# untitled.net
KiCad netlist of a schematic drawn in EAGLE
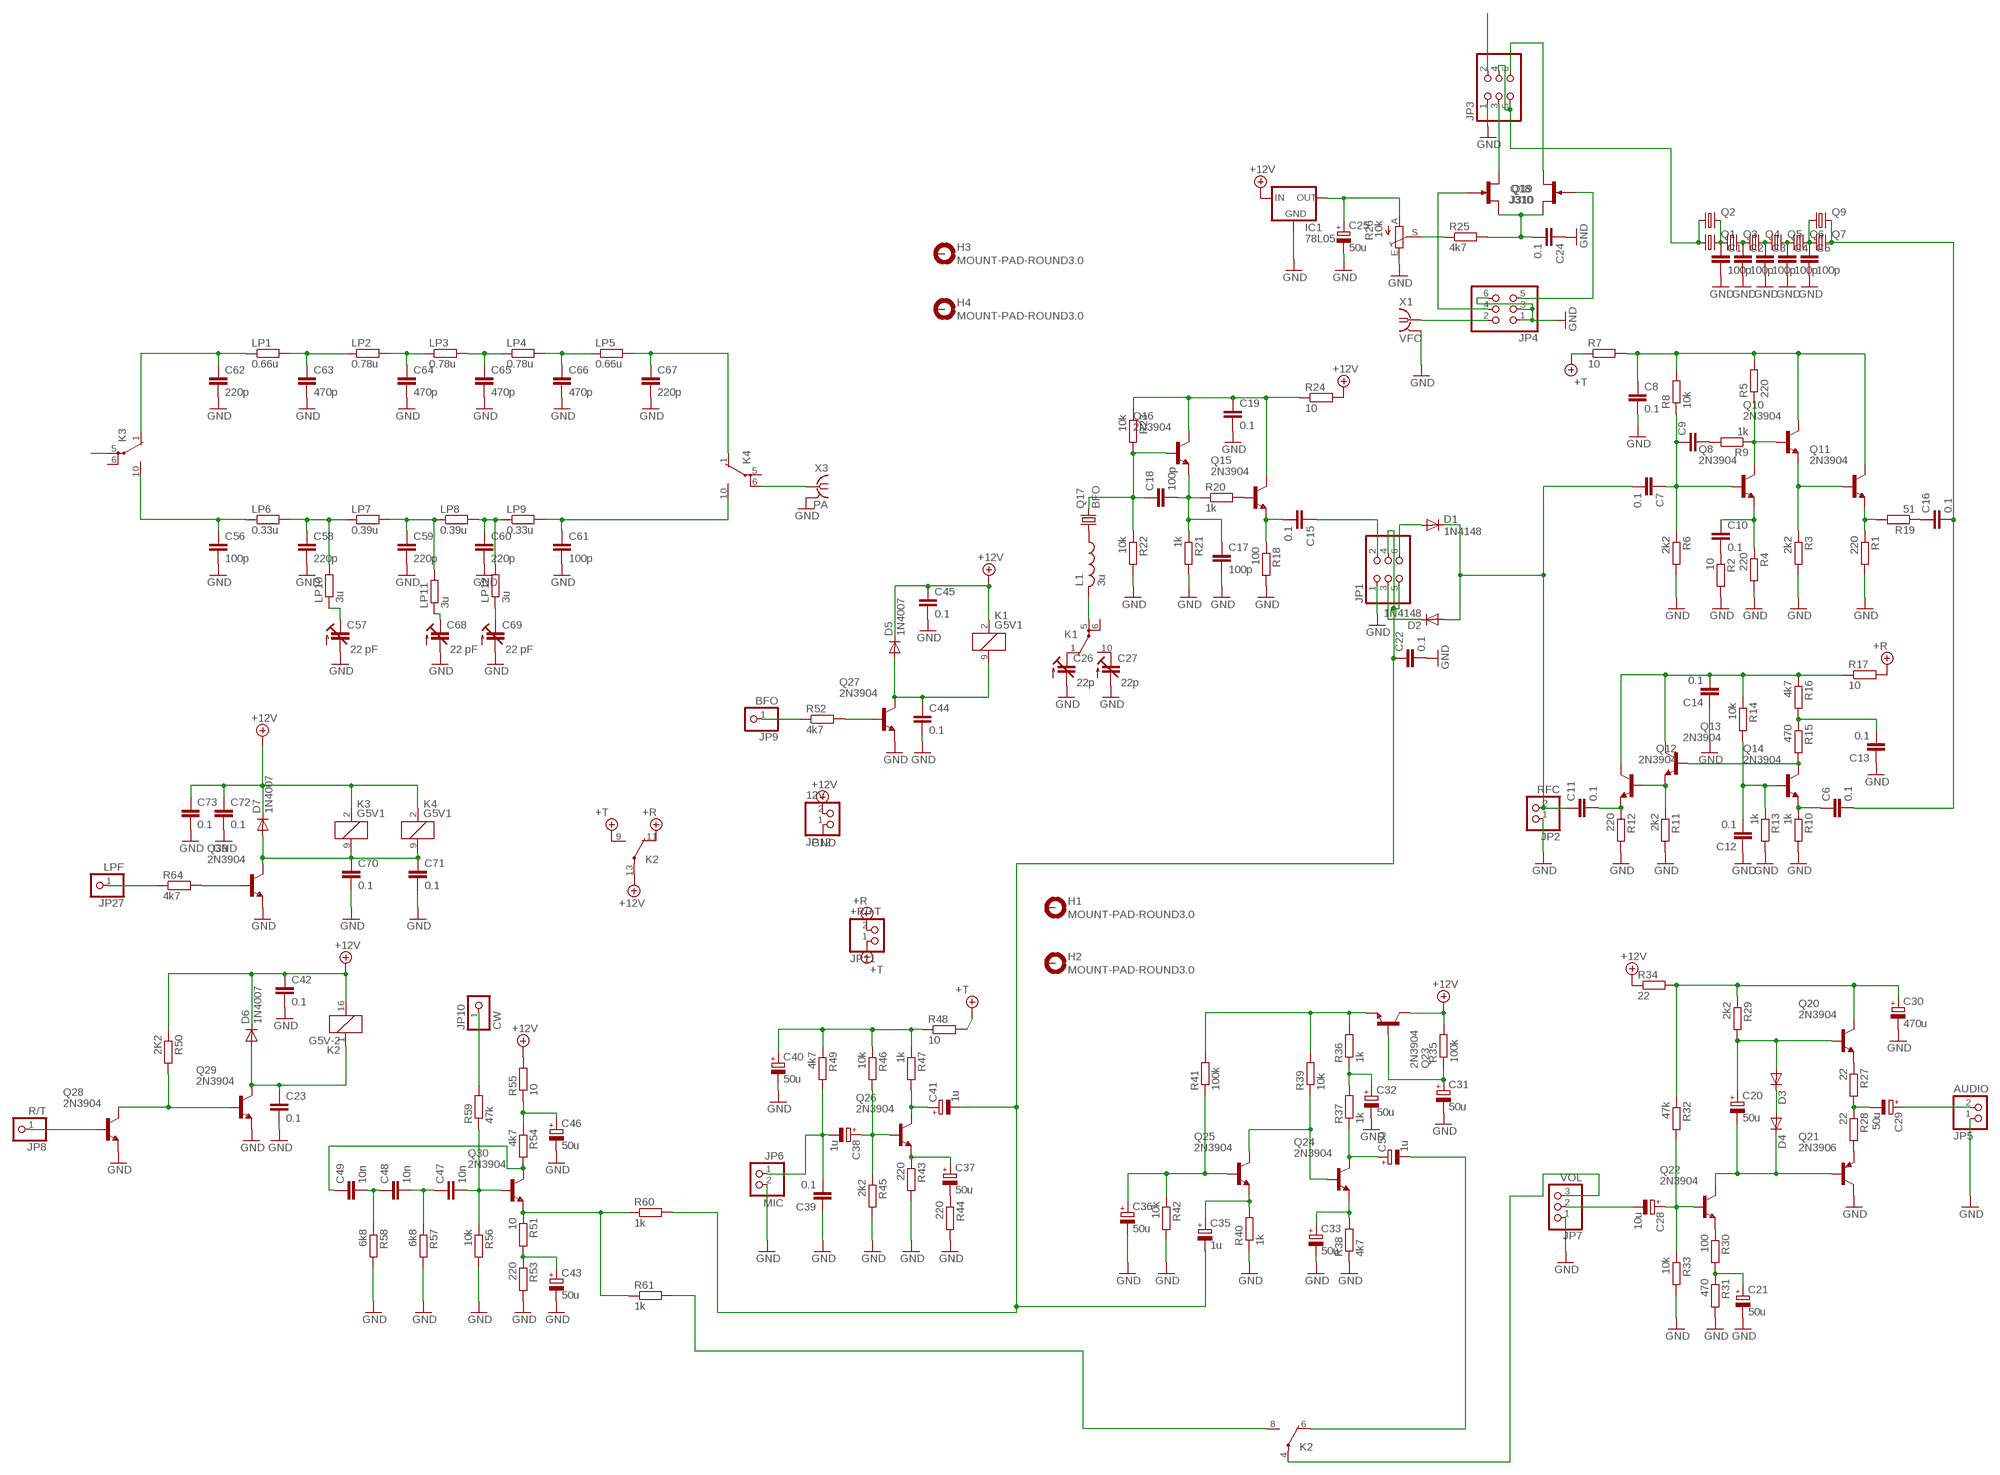
[diagram p0: schematic, sheet 1]

(export (version "E")
  (design (tool "Eeschema 10.0.6"))
  (components
    (comp (ref "C1")
      (value "100p")
      (footprint "eagle-import:C1206")
      (libsource (lib "eagle-import") (part "C-EUC1206"))
    )
    (comp (ref "C2")
      (value "100p")
      (footprint "eagle-import:C1206")
      (libsource (lib "eagle-import") (part "C-EUC1206"))
    )
    (comp (ref "C3")
      (value "100p")
      (footprint "eagle-import:C1206")
      (libsource (lib "eagle-import") (part "C-EUC1206"))
    )
    (comp (ref "C4")
      (value "100p")
      (footprint "eagle-import:C1206")
      (libsource (lib "eagle-import") (part "C-EUC1206"))
    )
    (comp (ref "C5")
      (value "100p")
      (footprint "eagle-import:C1206")
      (libsource (lib "eagle-import") (part "C-EUC1206"))
    )
    (comp (ref "C6")
      (value "0.1")
      (footprint "eagle-import:C050-024X044")
      (libsource (lib "eagle-import") (part "C-EU050-024X044"))
    )
    (comp (ref "C7")
      (value "0.1")
      (footprint "eagle-import:C050-024X044")
      (libsource (lib "eagle-import") (part "C-EU050-024X044"))
    )
    (comp (ref "C8")
      (value "0.1")
      (footprint "eagle-import:C050-024X044")
      (libsource (lib "eagle-import") (part "C-EU050-024X044"))
    )
    (comp (ref "C9")
      (value "C-EU050-024X044")
      (footprint "eagle-import:C050-024X044")
      (libsource (lib "eagle-import") (part "C-EU050-024X044"))
    )
    (comp (ref "C10")
      (value "0.1")
      (footprint "eagle-import:C050-024X044")
      (libsource (lib "eagle-import") (part "C-EU050-024X044"))
    )
    (comp (ref "C11")
      (value "0.1")
      (footprint "eagle-import:C050-024X044")
      (libsource (lib "eagle-import") (part "C-EU050-024X044"))
    )
    (comp (ref "C12")
      (value "0.1")
      (footprint "eagle-import:C050-024X044")
      (libsource (lib "eagle-import") (part "C-EU050-024X044"))
    )
    (comp (ref "C13")
      (value "0.1")
      (footprint "eagle-import:C050-024X044")
      (libsource (lib "eagle-import") (part "C-EU050-024X044"))
    )
    (comp (ref "C14")
      (value "0.1")
      (footprint "eagle-import:C050-024X044")
      (libsource (lib "eagle-import") (part "C-EU050-024X044"))
    )
    (comp (ref "C15")
      (value "0.1")
      (footprint "eagle-import:C050-024X044")
      (libsource (lib "eagle-import") (part "C-EU050-024X044"))
    )
    (comp (ref "C16")
      (value "0.1")
      (footprint "eagle-import:C050-024X044")
      (libsource (lib "eagle-import") (part "C-EU050-024X044"))
    )
    (comp (ref "C17")
      (value "100p")
      (footprint "eagle-import:C050-024X044")
      (libsource (lib "eagle-import") (part "C-EU050-024X044"))
    )
    (comp (ref "C18")
      (value "100p")
      (footprint "eagle-import:C050-024X044")
      (libsource (lib "eagle-import") (part "C-EU050-024X044"))
    )
    (comp (ref "C19")
      (value "0.1")
      (footprint "eagle-import:C050-024X044")
      (libsource (lib "eagle-import") (part "C-EU050-024X044"))
    )
    (comp (ref "C20")
      (value "50u")
      (footprint "eagle-import:E2,5-5")
      (libsource (lib "eagle-import") (part "CPOL-EUE2.5-5"))
    )
    (comp (ref "C21")
      (value "50u")
      (footprint "eagle-import:E2,5-5")
      (libsource (lib "eagle-import") (part "CPOL-EUE2.5-5"))
    )
    (comp (ref "C22")
      (value "0.1")
      (footprint "eagle-import:C050-024X044")
      (libsource (lib "eagle-import") (part "C-EU050-024X044"))
    )
    (comp (ref "C23")
      (value "0.1")
      (footprint "eagle-import:C050-024X044")
      (libsource (lib "eagle-import") (part "C-EU050-024X044"))
    )
    (comp (ref "C24")
      (value "0.1")
      (footprint "eagle-import:C050-024X044")
      (libsource (lib "eagle-import") (part "C-EU050-024X044"))
    )
    (comp (ref "C25")
      (value "50u")
      (footprint "eagle-import:E2,5-5")
      (libsource (lib "eagle-import") (part "CPOL-EUE2.5-5"))
    )
    (comp (ref "C26")
      (value "22p")
      (footprint "eagle-import:CTRIMTZ03")
      (libsource (lib "eagle-import") (part "C-TRIMMTZ03"))
    )
    (comp (ref "C27")
      (value "22p")
      (footprint "eagle-import:CTRIMTZ03")
      (libsource (lib "eagle-import") (part "C-TRIMMTZ03"))
    )
    (comp (ref "C28")
      (value "10u")
      (footprint "eagle-import:E2,5-5")
      (libsource (lib "eagle-import") (part "CPOL-EUE2.5-5"))
    )
    (comp (ref "C29")
      (value "50u")
      (footprint "eagle-import:E2,5-5")
      (libsource (lib "eagle-import") (part "CPOL-EUE2.5-5"))
    )
    (comp (ref "C30")
      (value "470u")
      (footprint "eagle-import:E2,5-5")
      (libsource (lib "eagle-import") (part "CPOL-EUE2.5-5"))
    )
    (comp (ref "C31")
      (value "50u")
      (footprint "eagle-import:E2,5-5")
      (libsource (lib "eagle-import") (part "CPOL-EUE2.5-5"))
    )
    (comp (ref "C32")
      (value "50u")
      (footprint "eagle-import:E2,5-5")
      (libsource (lib "eagle-import") (part "CPOL-EUE2.5-5"))
    )
    (comp (ref "C33")
      (value "50u")
      (footprint "eagle-import:E2,5-5")
      (libsource (lib "eagle-import") (part "CPOL-EUE2.5-5"))
    )
    (comp (ref "C35")
      (value "1u")
      (footprint "eagle-import:E2,5-5")
      (libsource (lib "eagle-import") (part "CPOL-EUE2.5-5"))
    )
    (comp (ref "C36")
      (value "50u")
      (footprint "eagle-import:E2,5-5")
      (libsource (lib "eagle-import") (part "CPOL-EUE2.5-5"))
    )
    (comp (ref "C37")
      (value "50u")
      (footprint "eagle-import:E2,5-5")
      (libsource (lib "eagle-import") (part "CPOL-EUE2.5-5"))
    )
    (comp (ref "C38")
      (value "1u")
      (footprint "eagle-import:E2,5-5")
      (libsource (lib "eagle-import") (part "CPOL-EUE2.5-5"))
    )
    (comp (ref "C39")
      (value "0.1")
      (footprint "eagle-import:C050-024X044")
      (libsource (lib "eagle-import") (part "C-EU050-024X044"))
    )
    (comp (ref "C40")
      (value "50u")
      (footprint "eagle-import:E2,5-5")
      (libsource (lib "eagle-import") (part "CPOL-EUE2.5-5"))
    )
    (comp (ref "C41")
      (value "1u")
      (footprint "eagle-import:E2,5-5")
      (libsource (lib "eagle-import") (part "CPOL-EUE2.5-5"))
    )
    (comp (ref "C42")
      (value "0.1")
      (footprint "eagle-import:C050-024X044")
      (libsource (lib "eagle-import") (part "C-EU050-024X044"))
    )
    (comp (ref "C43")
      (value "50u")
      (footprint "eagle-import:E2,5-5")
      (libsource (lib "eagle-import") (part "CPOL-EUE2.5-5"))
    )
    (comp (ref "C44")
      (value "0.1")
      (footprint "eagle-import:C050-024X044")
      (libsource (lib "eagle-import") (part "C-EU050-024X044"))
    )
    (comp (ref "C45")
      (value "0.1")
      (footprint "eagle-import:C050-024X044")
      (libsource (lib "eagle-import") (part "C-EU050-024X044"))
    )
    (comp (ref "C46")
      (value "50u")
      (footprint "eagle-import:E2,5-5")
      (libsource (lib "eagle-import") (part "CPOL-EUE2.5-5"))
    )
    (comp (ref "C47")
      (value "10n")
      (footprint "eagle-import:C050-024X044")
      (libsource (lib "eagle-import") (part "C-EU050-024X044"))
    )
    (comp (ref "C48")
      (value "10n")
      (footprint "eagle-import:C050-024X044")
      (libsource (lib "eagle-import") (part "C-EU050-024X044"))
    )
    (comp (ref "C49")
      (value "10n")
      (footprint "eagle-import:C050-024X044")
      (libsource (lib "eagle-import") (part "C-EU050-024X044"))
    )
    (comp (ref "C50")
      (value "1u")
      (footprint "eagle-import:E5-4")
      (libsource (lib "eagle-import") (part "CPOL-EUE5-4"))
    )
    (comp (ref "C56")
      (value "100p")
      (footprint "eagle-import:C050-024X044")
      (libsource (lib "eagle-import") (part "C-EU050-024X044"))
    )
    (comp (ref "C57")
      (value "22 pF")
      (footprint "eagle-import:CTRIMTZ03")
      (libsource (lib "eagle-import") (part "C-TRIMMTZ03"))
    )
    (comp (ref "C58")
      (value "220p")
      (footprint "eagle-import:C050-024X044")
      (libsource (lib "eagle-import") (part "C-EU050-024X044"))
    )
    (comp (ref "C59")
      (value "220p")
      (footprint "eagle-import:C050-024X044")
      (libsource (lib "eagle-import") (part "C-EU050-024X044"))
    )
    (comp (ref "C60")
      (value "220p")
      (footprint "eagle-import:C050-024X044")
      (libsource (lib "eagle-import") (part "C-EU050-024X044"))
    )
    (comp (ref "C61")
      (value "100p")
      (footprint "eagle-import:C050-024X044")
      (libsource (lib "eagle-import") (part "C-EU050-024X044"))
    )
    (comp (ref "C62")
      (value "220p")
      (footprint "eagle-import:C050-024X044")
      (libsource (lib "eagle-import") (part "C-EU050-024X044"))
    )
    (comp (ref "C63")
      (value "470p")
      (footprint "eagle-import:C050-024X044")
      (libsource (lib "eagle-import") (part "C-EU050-024X044"))
    )
    (comp (ref "C64")
      (value "470p")
      (footprint "eagle-import:C050-024X044")
      (libsource (lib "eagle-import") (part "C-EU050-024X044"))
    )
    (comp (ref "C65")
      (value "470p")
      (footprint "eagle-import:C050-024X044")
      (libsource (lib "eagle-import") (part "C-EU050-024X044"))
    )
    (comp (ref "C66")
      (value "470p")
      (footprint "eagle-import:C050-024X044")
      (libsource (lib "eagle-import") (part "C-EU050-024X044"))
    )
    (comp (ref "C67")
      (value "220p")
      (footprint "eagle-import:C050-024X044")
      (libsource (lib "eagle-import") (part "C-EU050-024X044"))
    )
    (comp (ref "C68")
      (value "22 pF")
      (footprint "eagle-import:CTRIMTZ03")
      (libsource (lib "eagle-import") (part "C-TRIMMTZ03"))
    )
    (comp (ref "C69")
      (value "22 pF")
      (footprint "eagle-import:CTRIMTZ03")
      (libsource (lib "eagle-import") (part "C-TRIMMTZ03"))
    )
    (comp (ref "C70")
      (value "0.1")
      (footprint "eagle-import:C050-024X044")
      (libsource (lib "eagle-import") (part "C-EU050-024X044"))
    )
    (comp (ref "C71")
      (value "0.1")
      (footprint "eagle-import:C050-024X044")
      (libsource (lib "eagle-import") (part "C-EU050-024X044"))
    )
    (comp (ref "C72")
      (value "0.1")
      (footprint "eagle-import:C050-024X044")
      (libsource (lib "eagle-import") (part "C-EU050-024X044"))
    )
    (comp (ref "C73")
      (value "0.1")
      (footprint "eagle-import:C050-024X044")
      (libsource (lib "eagle-import") (part "C-EU050-024X044"))
    )
    (comp (ref "D1")
      (value "1N4148")
      (footprint "eagle-import:D-5")
      (libsource (lib "eagle-import") (part "DIODE-D-5"))
    )
    (comp (ref "D2")
      (value "1N4148")
      (footprint "eagle-import:D-5")
      (libsource (lib "eagle-import") (part "DIODE-D-5"))
    )
    (comp (ref "D3")
      (value "DIODE-D-5")
      (footprint "eagle-import:D-5")
      (libsource (lib "eagle-import") (part "DIODE-D-5"))
    )
    (comp (ref "D4")
      (value "DIODE-D-5")
      (footprint "eagle-import:D-5")
      (libsource (lib "eagle-import") (part "DIODE-D-5"))
    )
    (comp (ref "D5")
      (value "1N4007")
      (footprint "eagle-import:D-5")
      (libsource (lib "eagle-import") (part "DIODE-D-5"))
    )
    (comp (ref "D6")
      (value "1N4007")
      (footprint "eagle-import:D-5")
      (libsource (lib "eagle-import") (part "DIODE-D-5"))
    )
    (comp (ref "D7")
      (value "1N4007")
      (footprint "eagle-import:D-5")
      (libsource (lib "eagle-import") (part "DIODE-D-5"))
    )
    (comp (ref "H1")
      (value "MOUNT-PAD-ROUND3.0")
      (footprint "eagle-import:3,0-PAD")
      (libsource (lib "eagle-import") (part "MOUNT-PAD-ROUND3.0"))
    )
    (comp (ref "H2")
      (value "MOUNT-PAD-ROUND3.0")
      (footprint "eagle-import:3,0-PAD")
      (libsource (lib "eagle-import") (part "MOUNT-PAD-ROUND3.0"))
    )
    (comp (ref "H3")
      (value "MOUNT-PAD-ROUND3.0")
      (footprint "eagle-import:3,0-PAD")
      (libsource (lib "eagle-import") (part "MOUNT-PAD-ROUND3.0"))
    )
    (comp (ref "H4")
      (value "MOUNT-PAD-ROUND3.0")
      (footprint "eagle-import:3,0-PAD")
      (libsource (lib "eagle-import") (part "MOUNT-PAD-ROUND3.0"))
    )
    (comp (ref "IC1")
      (value "78L05")
      (footprint "eagle-import:78LXX")
      (libsource (lib "eagle-import") (part "78LXX"))
    )
    (comp (ref "JP1")
      (value "PINHD-2X3")
      (footprint "eagle-import:2X03")
      (libsource (lib "eagle-import") (part "PINHD-2X3"))
    )
    (comp (ref "JP2")
      (value "RFC")
      (footprint "eagle-import:1X02")
      (libsource (lib "eagle-import") (part "PINHD-1X2"))
    )
    (comp (ref "JP3")
      (value "PINHD-2X3")
      (footprint "eagle-import:2X03")
      (libsource (lib "eagle-import") (part "PINHD-2X3"))
    )
    (comp (ref "JP4")
      (value "PINHD-2X3")
      (footprint "eagle-import:2X03")
      (libsource (lib "eagle-import") (part "PINHD-2X3"))
    )
    (comp (ref "JP5")
      (value "AUDIO")
      (footprint "eagle-import:1X02")
      (libsource (lib "eagle-import") (part "PINHD-1X2"))
    )
    (comp (ref "JP6")
      (value "MIC")
      (footprint "eagle-import:1X02")
      (libsource (lib "eagle-import") (part "PINHD-1X2"))
    )
    (comp (ref "JP7")
      (value "VOL")
      (footprint "eagle-import:1X03")
      (libsource (lib "eagle-import") (part "PINHD-1X3"))
    )
    (comp (ref "JP8")
      (value "R/T")
      (footprint "eagle-import:1X01")
      (libsource (lib "eagle-import") (part "PINHD-1X1"))
    )
    (comp (ref "JP9")
      (value "BFO")
      (footprint "eagle-import:1X01")
      (libsource (lib "eagle-import") (part "PINHD-1X1"))
    )
    (comp (ref "JP10")
      (value "CW")
      (footprint "eagle-import:1X01")
      (libsource (lib "eagle-import") (part "PINHD-1X1"))
    )
    (comp (ref "JP11")
      (value "+R/+T")
      (footprint "eagle-import:1X02")
      (libsource (lib "eagle-import") (part "PINHD-1X2"))
    )
    (comp (ref "JP12")
      (value "12V")
      (footprint "eagle-import:1X02")
      (libsource (lib "eagle-import") (part "PINHD-1X2"))
    )
    (comp (ref "JP27")
      (value "LPF")
      (footprint "eagle-import:1X01")
      (libsource (lib "eagle-import") (part "PINHD-1X1"))
    )
    (comp (ref "K1")
      (value "G5V1")
      (footprint "eagle-import:G5V1")
      (fields (field (name "MPN") "G5V-1-DC24"))
      (libsource (lib "eagle-import") (part "G5V1"))
    )
    (comp (ref "K2")
      (value "G5V-2")
      (footprint "eagle-import:G5V-2")
      (fields (field (name "MPN") "G5V-2 5DC"))
      (libsource (lib "eagle-import") (part "G5V-2"))
    )
    (comp (ref "K3")
      (value "G5V1")
      (footprint "eagle-import:G5V1")
      (fields (field (name "MPN") "G5V-1-DC24"))
      (libsource (lib "eagle-import") (part "G5V1"))
    )
    (comp (ref "K4")
      (value "G5V1")
      (footprint "eagle-import:G5V1")
      (fields (field (name "MPN") "G5V-1-DC24"))
      (libsource (lib "eagle-import") (part "G5V1"))
    )
    (comp (ref "L1")
      (value "3u")
      (footprint "eagle-import:0207_2V")
      (libsource (lib "eagle-import") (part "L-US0207/2V"))
    )
    (comp (ref "LP1")
      (value "0.66u")
      (footprint "eagle-import:0204_5")
      (libsource (lib "eagle-import") (part "R-EU_0204/5"))
    )
    (comp (ref "LP2")
      (value "0.78u")
      (footprint "eagle-import:0204_5")
      (libsource (lib "eagle-import") (part "R-EU_0204/5"))
    )
    (comp (ref "LP3")
      (value "0.78u")
      (footprint "eagle-import:0204_5")
      (libsource (lib "eagle-import") (part "R-EU_0204/5"))
    )
    (comp (ref "LP4")
      (value "0.78u")
      (footprint "eagle-import:0204_5")
      (libsource (lib "eagle-import") (part "R-EU_0204/5"))
    )
    (comp (ref "LP5")
      (value "0.66u")
      (footprint "eagle-import:0204_5")
      (libsource (lib "eagle-import") (part "R-EU_0204/5"))
    )
    (comp (ref "LP6")
      (value "0.33u")
      (footprint "eagle-import:0204_5")
      (libsource (lib "eagle-import") (part "R-EU_0204/5"))
    )
    (comp (ref "LP7")
      (value "0.39u")
      (footprint "eagle-import:0204_5")
      (libsource (lib "eagle-import") (part "R-EU_0204/5"))
    )
    (comp (ref "LP8")
      (value "0.39u")
      (footprint "eagle-import:0204_5")
      (libsource (lib "eagle-import") (part "R-EU_0204/5"))
    )
    (comp (ref "LP9")
      (value "0.33u")
      (footprint "eagle-import:0204_5")
      (libsource (lib "eagle-import") (part "R-EU_0204/5"))
    )
    (comp (ref "LP10")
      (value "3u")
      (footprint "eagle-import:0204_5")
      (libsource (lib "eagle-import") (part "R-EU_0204/5"))
    )
    (comp (ref "LP11")
      (value "3u")
      (footprint "eagle-import:0204_5")
      (libsource (lib "eagle-import") (part "R-EU_0204/5"))
    )
    (comp (ref "LP12")
      (value "3u")
      (footprint "eagle-import:0204_5")
      (libsource (lib "eagle-import") (part "R-EU_0204/5"))
    )
    (comp (ref "Q1")
      (value "CRYSTALHC49S")
      (footprint "eagle-import:HC49_S")
      (libsource (lib "eagle-import") (part "CRYSTALHC49S"))
    )
    (comp (ref "Q2")
      (value "CRYSTALHC49S")
      (footprint "eagle-import:HC49_S")
      (libsource (lib "eagle-import") (part "CRYSTALHC49S"))
    )
    (comp (ref "Q3")
      (value "CRYSTALHC49S")
      (footprint "eagle-import:HC49_S")
      (libsource (lib "eagle-import") (part "CRYSTALHC49S"))
    )
    (comp (ref "Q4")
      (value "CRYSTALHC49S")
      (footprint "eagle-import:HC49_S")
      (libsource (lib "eagle-import") (part "CRYSTALHC49S"))
    )
    (comp (ref "Q5")
      (value "CRYSTALHC49S")
      (footprint "eagle-import:HC49_S")
      (libsource (lib "eagle-import") (part "CRYSTALHC49S"))
    )
    (comp (ref "Q6")
      (value "CRYSTALHC49S")
      (footprint "eagle-import:HC49_S")
      (libsource (lib "eagle-import") (part "CRYSTALHC49S"))
    )
    (comp (ref "Q7")
      (value "CRYSTALHC49S")
      (footprint "eagle-import:HC49_S")
      (libsource (lib "eagle-import") (part "CRYSTALHC49S"))
    )
    (comp (ref "Q8")
      (value "2N3904")
      (footprint "eagle-import:TO92")
      (libsource (lib "eagle-import") (part "2N3904"))
    )
    (comp (ref "Q9")
      (value "CRYSTALHC49S")
      (footprint "eagle-import:HC49_S")
      (libsource (lib "eagle-import") (part "CRYSTALHC49S"))
    )
    (comp (ref "Q10")
      (value "2N3904")
      (footprint "eagle-import:TO92")
      (libsource (lib "eagle-import") (part "2N3904"))
    )
    (comp (ref "Q11")
      (value "2N3904")
      (footprint "eagle-import:TO92")
      (libsource (lib "eagle-import") (part "2N3904"))
    )
    (comp (ref "Q12")
      (value "2N3904")
      (footprint "eagle-import:TO92")
      (libsource (lib "eagle-import") (part "2N3904"))
    )
    (comp (ref "Q13")
      (value "2N3904")
      (footprint "eagle-import:TO92")
      (libsource (lib "eagle-import") (part "2N3904"))
    )
    (comp (ref "Q14")
      (value "2N3904")
      (footprint "eagle-import:TO92")
      (libsource (lib "eagle-import") (part "2N3904"))
    )
    (comp (ref "Q15")
      (value "2N3904")
      (footprint "eagle-import:TO92")
      (libsource (lib "eagle-import") (part "2N3904"))
    )
    (comp (ref "Q16")
      (value "2N3904")
      (footprint "eagle-import:TO92")
      (libsource (lib "eagle-import") (part "2N3904"))
    )
    (comp (ref "Q17")
      (value "BFO")
      (footprint "eagle-import:HC49_S")
      (fields (field (name "OC_FARNELL") "1667008") (field (name "OC_NEWARK") "unknown"))
      (libsource (lib "eagle-import") (part "CRYSTALHC49S"))
    )
    (comp (ref "Q18")
      (value "J310")
      (footprint "eagle-import:TO92R")
      (libsource (lib "eagle-import") (part "J310"))
    )
    (comp (ref "Q19")
      (value "J310")
      (footprint "eagle-import:TO92R")
      (libsource (lib "eagle-import") (part "J310"))
    )
    (comp (ref "Q20")
      (value "2N3904")
      (footprint "eagle-import:TO92")
      (libsource (lib "eagle-import") (part "2N3904"))
    )
    (comp (ref "Q21")
      (value "2N3906")
      (footprint "eagle-import:TO92")
      (libsource (lib "eagle-import") (part "2N3906"))
    )
    (comp (ref "Q22")
      (value "2N3904")
      (footprint "eagle-import:TO92")
      (libsource (lib "eagle-import") (part "2N3904"))
    )
    (comp (ref "Q23")
      (value "2N3904")
      (footprint "eagle-import:TO92")
      (libsource (lib "eagle-import") (part "2N3904"))
    )
    (comp (ref "Q24")
      (value "2N3904")
      (footprint "eagle-import:TO92")
      (libsource (lib "eagle-import") (part "2N3904"))
    )
    (comp (ref "Q25")
      (value "2N3904")
      (footprint "eagle-import:TO92")
      (libsource (lib "eagle-import") (part "2N3904"))
    )
    (comp (ref "Q26")
      (value "2N3904")
      (footprint "eagle-import:TO92")
      (libsource (lib "eagle-import") (part "2N3904"))
    )
    (comp (ref "Q27")
      (value "2N3904")
      (footprint "eagle-import:TO92")
      (libsource (lib "eagle-import") (part "2N3904"))
    )
    (comp (ref "Q28")
      (value "2N3904")
      (footprint "eagle-import:TO92")
      (libsource (lib "eagle-import") (part "2N3904"))
    )
    (comp (ref "Q29")
      (value "2N3904")
      (footprint "eagle-import:TO92")
      (libsource (lib "eagle-import") (part "2N3904"))
    )
    (comp (ref "Q30")
      (value "2N3904")
      (footprint "eagle-import:TO92")
      (libsource (lib "eagle-import") (part "2N3904"))
    )
    (comp (ref "Q39")
      (value "2N3904")
      (footprint "eagle-import:TO92")
      (libsource (lib "eagle-import") (part "2N3904"))
    )
    (comp (ref "R1")
      (value "220")
      (footprint "eagle-import:0204_5")
      (libsource (lib "eagle-import") (part "R-EU_0204/5"))
    )
    (comp (ref "R2")
      (value "10")
      (footprint "eagle-import:0204_5")
      (libsource (lib "eagle-import") (part "R-EU_0204/5"))
    )
    (comp (ref "R3")
      (value "2k2")
      (footprint "eagle-import:0204_5")
      (libsource (lib "eagle-import") (part "R-EU_0204/5"))
    )
    (comp (ref "R4")
      (value "220")
      (footprint "eagle-import:0204_5")
      (libsource (lib "eagle-import") (part "R-EU_0204/5"))
    )
    (comp (ref "R5")
      (value "220")
      (footprint "eagle-import:0204_5")
      (libsource (lib "eagle-import") (part "R-EU_0204/5"))
    )
    (comp (ref "R6")
      (value "2k2")
      (footprint "eagle-import:0204_5")
      (libsource (lib "eagle-import") (part "R-EU_0204/5"))
    )
    (comp (ref "R7")
      (value "10")
      (footprint "eagle-import:0204_5")
      (libsource (lib "eagle-import") (part "R-EU_0204/5"))
    )
    (comp (ref "R8")
      (value "10k")
      (footprint "eagle-import:0204_5")
      (libsource (lib "eagle-import") (part "R-EU_0204/5"))
    )
    (comp (ref "R9")
      (value "1k")
      (footprint "eagle-import:0204_5")
      (libsource (lib "eagle-import") (part "R-EU_0204/5"))
    )
    (comp (ref "R10")
      (value "1k")
      (footprint "eagle-import:0204_5")
      (libsource (lib "eagle-import") (part "R-EU_0204/5"))
    )
    (comp (ref "R11")
      (value "2k2")
      (footprint "eagle-import:0204_5")
      (libsource (lib "eagle-import") (part "R-EU_0204/5"))
    )
    (comp (ref "R12")
      (value "220")
      (footprint "eagle-import:0204_5")
      (libsource (lib "eagle-import") (part "R-EU_0204/5"))
    )
    (comp (ref "R13")
      (value "1k")
      (footprint "eagle-import:0204_5")
      (libsource (lib "eagle-import") (part "R-EU_0204/5"))
    )
    (comp (ref "R14")
      (value "10k")
      (footprint "eagle-import:0204_5")
      (libsource (lib "eagle-import") (part "R-EU_0204/5"))
    )
    (comp (ref "R15")
      (value "470")
      (footprint "eagle-import:0204_5")
      (libsource (lib "eagle-import") (part "R-EU_0204/5"))
    )
    (comp (ref "R16")
      (value "4k7")
      (footprint "eagle-import:0204_5")
      (libsource (lib "eagle-import") (part "R-EU_0204/5"))
    )
    (comp (ref "R17")
      (value "10")
      (footprint "eagle-import:0204_5")
      (libsource (lib "eagle-import") (part "R-EU_0204/5"))
    )
    (comp (ref "R18")
      (value "100")
      (footprint "eagle-import:0204_5")
      (libsource (lib "eagle-import") (part "R-EU_0204/5"))
    )
    (comp (ref "R19")
      (value "51")
      (footprint "eagle-import:0204_5")
      (libsource (lib "eagle-import") (part "R-EU_0204/5"))
    )
    (comp (ref "R20")
      (value "1k")
      (footprint "eagle-import:0204_5")
      (libsource (lib "eagle-import") (part "R-EU_0204/5"))
    )
    (comp (ref "R21")
      (value "1k")
      (footprint "eagle-import:0204_5")
      (libsource (lib "eagle-import") (part "R-EU_0204/5"))
    )
    (comp (ref "R22")
      (value "10k")
      (footprint "eagle-import:0204_5")
      (libsource (lib "eagle-import") (part "R-EU_0204/5"))
    )
    (comp (ref "R23")
      (value "10k")
      (footprint "eagle-import:0204_5")
      (libsource (lib "eagle-import") (part "R-EU_0204/5"))
    )
    (comp (ref "R24")
      (value "10")
      (footprint "eagle-import:0204_5")
      (libsource (lib "eagle-import") (part "R-EU_0204/5"))
    )
    (comp (ref "R25")
      (value "4k7")
      (footprint "eagle-import:0204_5")
      (libsource (lib "eagle-import") (part "R-EU_0204/5"))
    )
    (comp (ref "R26")
      (value "10k")
      (footprint "eagle-import:CA6V")
      (libsource (lib "eagle-import") (part "TRIM_EU-CA6V"))
    )
    (comp (ref "R27")
      (value "22")
      (footprint "eagle-import:0204_5")
      (libsource (lib "eagle-import") (part "R-EU_0204/5"))
    )
    (comp (ref "R28")
      (value "22")
      (footprint "eagle-import:0204_5")
      (libsource (lib "eagle-import") (part "R-EU_0204/5"))
    )
    (comp (ref "R29")
      (value "2k2")
      (footprint "eagle-import:0204_5")
      (libsource (lib "eagle-import") (part "R-EU_0204/5"))
    )
    (comp (ref "R30")
      (value "100")
      (footprint "eagle-import:0204_5")
      (libsource (lib "eagle-import") (part "R-EU_0204/5"))
    )
    (comp (ref "R31")
      (value "470")
      (footprint "eagle-import:0204_5")
      (libsource (lib "eagle-import") (part "R-EU_0204/5"))
    )
    (comp (ref "R32")
      (value "47k")
      (footprint "eagle-import:0204_5")
      (libsource (lib "eagle-import") (part "R-EU_0204/5"))
    )
    (comp (ref "R33")
      (value "10k")
      (footprint "eagle-import:0204_5")
      (libsource (lib "eagle-import") (part "R-EU_0204/5"))
    )
    (comp (ref "R34")
      (value "22")
      (footprint "eagle-import:0204_5")
      (libsource (lib "eagle-import") (part "R-EU_0204/5"))
    )
    (comp (ref "R35")
      (value "100k")
      (footprint "eagle-import:0204_5")
      (libsource (lib "eagle-import") (part "R-EU_0204/5"))
    )
    (comp (ref "R36")
      (value "1k")
      (footprint "eagle-import:0204_5")
      (libsource (lib "eagle-import") (part "R-EU_0204/5"))
    )
    (comp (ref "R37")
      (value "1k")
      (footprint "eagle-import:0204_5")
      (libsource (lib "eagle-import") (part "R-EU_0204/5"))
    )
    (comp (ref "R38")
      (value "4k7")
      (footprint "eagle-import:0204_5")
      (libsource (lib "eagle-import") (part "R-EU_0204/5"))
    )
    (comp (ref "R39")
      (value "10k")
      (footprint "eagle-import:0204_5")
      (libsource (lib "eagle-import") (part "R-EU_0204/5"))
    )
    (comp (ref "R40")
      (value "1k")
      (footprint "eagle-import:0204_5")
      (libsource (lib "eagle-import") (part "R-EU_0204/5"))
    )
    (comp (ref "R41")
      (value "100k")
      (footprint "eagle-import:0204_5")
      (libsource (lib "eagle-import") (part "R-EU_0204/5"))
    )
    (comp (ref "R42")
      (value "10k")
      (footprint "eagle-import:0204_5")
      (libsource (lib "eagle-import") (part "R-EU_0204/5"))
    )
    (comp (ref "R43")
      (value "220")
      (footprint "eagle-import:0204_5")
      (libsource (lib "eagle-import") (part "R-EU_0204/5"))
    )
    (comp (ref "R44")
      (value "220")
      (footprint "eagle-import:0204_5")
      (libsource (lib "eagle-import") (part "R-EU_0204/5"))
    )
    (comp (ref "R45")
      (value "2k2")
      (footprint "eagle-import:0204_5")
      (libsource (lib "eagle-import") (part "R-EU_0204/5"))
    )
    (comp (ref "R46")
      (value "10k")
      (footprint "eagle-import:0204_5")
      (libsource (lib "eagle-import") (part "R-EU_0204/5"))
    )
    (comp (ref "R47")
      (value "1k")
      (footprint "eagle-import:0204_5")
      (libsource (lib "eagle-import") (part "R-EU_0204/5"))
    )
    (comp (ref "R48")
      (value "10")
      (footprint "eagle-import:0204_5")
      (libsource (lib "eagle-import") (part "R-EU_0204/5"))
    )
    (comp (ref "R49")
      (value "4k7")
      (footprint "eagle-import:0204_5")
      (libsource (lib "eagle-import") (part "R-EU_0204/5"))
    )
    (comp (ref "R50")
      (value "2K2")
      (footprint "eagle-import:0204_5")
      (libsource (lib "eagle-import") (part "R-EU_0204/5"))
    )
    (comp (ref "R51")
      (value "10")
      (footprint "eagle-import:0204_5")
      (libsource (lib "eagle-import") (part "R-EU_0204/5"))
    )
    (comp (ref "R52")
      (value "4k7")
      (footprint "eagle-import:0204_5")
      (libsource (lib "eagle-import") (part "R-EU_0204/5"))
    )
    (comp (ref "R53")
      (value "220")
      (footprint "eagle-import:0204_5")
      (libsource (lib "eagle-import") (part "R-EU_0204/5"))
    )
    (comp (ref "R54")
      (value "4k7")
      (footprint "eagle-import:0204_5")
      (libsource (lib "eagle-import") (part "R-EU_0204/5"))
    )
    (comp (ref "R55")
      (value "10")
      (footprint "eagle-import:0204_5")
      (libsource (lib "eagle-import") (part "R-EU_0204/5"))
    )
    (comp (ref "R56")
      (value "10k")
      (footprint "eagle-import:0204_5")
      (libsource (lib "eagle-import") (part "R-EU_0204/5"))
    )
    (comp (ref "R57")
      (value "6k8")
      (footprint "eagle-import:0204_5")
      (libsource (lib "eagle-import") (part "R-EU_0204/5"))
    )
    (comp (ref "R58")
      (value "6k8")
      (footprint "eagle-import:0204_5")
      (libsource (lib "eagle-import") (part "R-EU_0204/5"))
    )
    (comp (ref "R59")
      (value "47k")
      (footprint "eagle-import:0204_5")
      (libsource (lib "eagle-import") (part "R-EU_0204/5"))
    )
    (comp (ref "R60")
      (value "1k")
      (footprint "eagle-import:0204_5")
      (libsource (lib "eagle-import") (part "R-EU_0204/5"))
    )
    (comp (ref "R61")
      (value "1k")
      (footprint "eagle-import:0204_5")
      (libsource (lib "eagle-import") (part "R-EU_0204/5"))
    )
    (comp (ref "R64")
      (value "4k7")
      (footprint "eagle-import:0204_5")
      (libsource (lib "eagle-import") (part "R-EU_0204/5"))
    )
    (comp (ref "X1")
      (value "VFO")
      (footprint "eagle-import:BU-SMA-V")
      (libsource (lib "eagle-import") (part "BU-SMA-V"))
    )
    (comp (ref "X3")
      (value "PA")
      (footprint "eagle-import:BU-SMA-V")
      (fields (field (name "OC_FARNELL") "unknown") (field (name "OC_NEWARK") "unknown"))
      (libsource (lib "eagle-import") (part "BU-SMA-V"))
    )
  )
  (nets
    (net (code "1") (name "+12V") (class "Default")
      (node (ref "C42") (pin "1") (pinfunction "1_1") (pintype "passive"))
      (node (ref "C45") (pin "1") (pinfunction "1_1") (pintype "passive"))
      (node (ref "C72") (pin "1") (pinfunction "1_1") (pintype "passive"))
      (node (ref "C73") (pin "1") (pinfunction "1_1") (pintype "passive"))
      (node (ref "D5") (pin "C") (pinfunction "C_C") (pintype "passive"))
      (node (ref "D6") (pin "C") (pinfunction "C_C") (pintype "passive"))
      (node (ref "D7") (pin "C") (pinfunction "C_C") (pintype "passive"))
      (node (ref "IC1") (pin "IN") (pinfunction "IN_IN") (pintype "input"))
      (node (ref "JP12") (pin "2") (pinfunction "2_2") (pintype "passive"))
      (node (ref "K1") (pin "2") (pinfunction "1_2") (pintype "passive"))
      (node (ref "K2") (pin "13") (pinfunction "P_13") (pintype "passive"))
      (node (ref "K2") (pin "16") (pinfunction "2_16") (pintype "passive"))
      (node (ref "K3") (pin "2") (pinfunction "1_2") (pintype "passive"))
      (node (ref "K4") (pin "2") (pinfunction "1_2") (pintype "passive"))
      (node (ref "Q23") (pin "1") (pinfunction "C_1") (pintype "passive"))
      (node (ref "R24") (pin "2") (pinfunction "2_2") (pintype "passive"))
      (node (ref "R34") (pin "1") (pinfunction "1_1") (pintype "passive"))
      (node (ref "R35") (pin "2") (pinfunction "2_2") (pintype "passive"))
      (node (ref "R50") (pin "1") (pinfunction "1_1") (pintype "passive"))
      (node (ref "R55") (pin "2") (pinfunction "2_2") (pintype "passive"))
    )
    (net (code "2") (name "+R") (class "Default")
      (node (ref "JP11") (pin "2") (pinfunction "2_2") (pintype "passive"))
      (node (ref "K2") (pin "11") (pinfunction "O_11") (pintype "passive"))
      (node (ref "R17") (pin "2") (pinfunction "2_2") (pintype "passive"))
    )
    (net (code "3") (name "+T") (class "Default")
      (node (ref "JP11") (pin "1") (pinfunction "1_1") (pintype "passive"))
      (node (ref "K2") (pin "9") (pinfunction "S_9") (pintype "passive"))
      (node (ref "R48") (pin "2") (pinfunction "2_2") (pintype "passive"))
      (node (ref "R7") (pin "1") (pinfunction "1_1") (pintype "passive"))
    )
    (net (code "4") (name "/N$116") (class "Default")
      (node (ref "JP3") (pin "2") (pinfunction "2_2") (pintype "passive"))
      (node (ref "K3") (pin "5") (pinfunction "P_5") (pintype "passive"))
    )
    (net (code "5") (name "GND") (class "Default")
      (node (ref "C1") (pin "2") (pinfunction "2_2") (pintype "passive"))
      (node (ref "C12") (pin "1") (pinfunction "1_1") (pintype "passive"))
      (node (ref "C13") (pin "1") (pinfunction "1_1") (pintype "passive"))
      (node (ref "C14") (pin "1") (pinfunction "1_1") (pintype "passive"))
      (node (ref "C17") (pin "2") (pinfunction "2_2") (pintype "passive"))
      (node (ref "C19") (pin "2") (pinfunction "2_2") (pintype "passive"))
      (node (ref "C2") (pin "2") (pinfunction "2_2") (pintype "passive"))
      (node (ref "C21") (pin "-") (pinfunction "-_-") (pintype "passive"))
      (node (ref "C22") (pin "2") (pinfunction "2_2") (pintype "passive"))
      (node (ref "C23") (pin "2") (pinfunction "2_2") (pintype "passive"))
      (node (ref "C24") (pin "1") (pinfunction "1_1") (pintype "passive"))
      (node (ref "C25") (pin "-") (pinfunction "-_-") (pintype "passive"))
      (node (ref "C26") (pin "2") (pinfunction "A_2") (pintype "passive"))
      (node (ref "C27") (pin "2") (pinfunction "A_2") (pintype "passive"))
      (node (ref "C3") (pin "2") (pinfunction "2_2") (pintype "passive"))
      (node (ref "C30") (pin "-") (pinfunction "-_-") (pintype "passive"))
      (node (ref "C31") (pin "-") (pinfunction "-_-") (pintype "passive"))
      (node (ref "C32") (pin "-") (pinfunction "-_-") (pintype "passive"))
      (node (ref "C33") (pin "-") (pinfunction "-_-") (pintype "passive"))
      (node (ref "C36") (pin "-") (pinfunction "-_-") (pintype "passive"))
      (node (ref "C39") (pin "1") (pinfunction "1_1") (pintype "passive"))
      (node (ref "C4") (pin "2") (pinfunction "2_2") (pintype "passive"))
      (node (ref "C40") (pin "-") (pinfunction "-_-") (pintype "passive"))
      (node (ref "C42") (pin "2") (pinfunction "2_2") (pintype "passive"))
      (node (ref "C43") (pin "-") (pinfunction "-_-") (pintype "passive"))
      (node (ref "C44") (pin "2") (pinfunction "2_2") (pintype "passive"))
      (node (ref "C45") (pin "2") (pinfunction "2_2") (pintype "passive"))
      (node (ref "C46") (pin "-") (pinfunction "-_-") (pintype "passive"))
      (node (ref "C5") (pin "2") (pinfunction "2_2") (pintype "passive"))
      (node (ref "C56") (pin "2") (pinfunction "2_2") (pintype "passive"))
      (node (ref "C57") (pin "2") (pinfunction "A_2") (pintype "passive"))
      (node (ref "C58") (pin "2") (pinfunction "2_2") (pintype "passive"))
      (node (ref "C59") (pin "2") (pinfunction "2_2") (pintype "passive"))
      (node (ref "C60") (pin "2") (pinfunction "2_2") (pintype "passive"))
      (node (ref "C61") (pin "2") (pinfunction "2_2") (pintype "passive"))
      (node (ref "C62") (pin "2") (pinfunction "2_2") (pintype "passive"))
      (node (ref "C63") (pin "2") (pinfunction "2_2") (pintype "passive"))
      (node (ref "C64") (pin "2") (pinfunction "2_2") (pintype "passive"))
      (node (ref "C65") (pin "2") (pinfunction "2_2") (pintype "passive"))
      (node (ref "C66") (pin "2") (pinfunction "2_2") (pintype "passive"))
      (node (ref "C67") (pin "2") (pinfunction "2_2") (pintype "passive"))
      (node (ref "C68") (pin "2") (pinfunction "A_2") (pintype "passive"))
      (node (ref "C69") (pin "2") (pinfunction "A_2") (pintype "passive"))
      (node (ref "C70") (pin "2") (pinfunction "2_2") (pintype "passive"))
      (node (ref "C71") (pin "2") (pinfunction "2_2") (pintype "passive"))
      (node (ref "C72") (pin "2") (pinfunction "2_2") (pintype "passive"))
      (node (ref "C73") (pin "2") (pinfunction "2_2") (pintype "passive"))
      (node (ref "C8") (pin "2") (pinfunction "2_2") (pintype "passive"))
      (node (ref "IC1") (pin "GND") (pinfunction "GND_GND") (pintype "input"))
      (node (ref "JP1") (pin "1") (pinfunction "1_1") (pintype "passive"))
      (node (ref "JP12") (pin "1") (pinfunction "1_1") (pintype "passive"))
      (node (ref "JP2") (pin "1") (pinfunction "1_1") (pintype "passive"))
      (node (ref "JP3") (pin "1") (pinfunction "1_1") (pintype "passive"))
      (node (ref "JP4") (pin "1") (pinfunction "1_1") (pintype "passive"))
      (node (ref "JP4") (pin "3") (pinfunction "3_3") (pintype "passive"))
      (node (ref "JP4") (pin "6") (pinfunction "6_6") (pintype "passive"))
      (node (ref "JP5") (pin "1") (pinfunction "1_1") (pintype "passive"))
      (node (ref "JP6") (pin "2") (pinfunction "2_2") (pintype "passive"))
      (node (ref "JP7") (pin "1") (pinfunction "1_1") (pintype "passive"))
      (node (ref "Q21") (pin "1") (pinfunction "C_1") (pintype "passive"))
      (node (ref "Q27") (pin "3") (pinfunction "E_3") (pintype "passive"))
      (node (ref "Q28") (pin "3") (pinfunction "E_3") (pintype "passive"))
      (node (ref "Q29") (pin "3") (pinfunction "E_3") (pintype "passive"))
      (node (ref "Q39") (pin "3") (pinfunction "E_3") (pintype "passive"))
      (node (ref "R1") (pin "2") (pinfunction "2_2") (pintype "passive"))
      (node (ref "R10") (pin "2") (pinfunction "2_2") (pintype "passive"))
      (node (ref "R11") (pin "2") (pinfunction "2_2") (pintype "passive"))
      (node (ref "R12") (pin "2") (pinfunction "2_2") (pintype "passive"))
      (node (ref "R13") (pin "2") (pinfunction "2_2") (pintype "passive"))
      (node (ref "R18") (pin "2") (pinfunction "2_2") (pintype "passive"))
      (node (ref "R2") (pin "2") (pinfunction "2_2") (pintype "passive"))
      (node (ref "R21") (pin "2") (pinfunction "2_2") (pintype "passive"))
      (node (ref "R22") (pin "2") (pinfunction "2_2") (pintype "passive"))
      (node (ref "R26") (pin "E") (pinfunction "E_E") (pintype "passive"))
      (node (ref "R3") (pin "2") (pinfunction "2_2") (pintype "passive"))
      (node (ref "R31") (pin "2") (pinfunction "2_2") (pintype "passive"))
      (node (ref "R33") (pin "2") (pinfunction "2_2") (pintype "passive"))
      (node (ref "R38") (pin "1") (pinfunction "1_1") (pintype "passive"))
      (node (ref "R4") (pin "2") (pinfunction "2_2") (pintype "passive"))
      (node (ref "R40") (pin "1") (pinfunction "1_1") (pintype "passive"))
      (node (ref "R42") (pin "2") (pinfunction "2_2") (pintype "passive"))
      (node (ref "R43") (pin "2") (pinfunction "2_2") (pintype "passive"))
      (node (ref "R44") (pin "2") (pinfunction "2_2") (pintype "passive"))
      (node (ref "R45") (pin "2") (pinfunction "2_2") (pintype "passive"))
      (node (ref "R53") (pin "2") (pinfunction "2_2") (pintype "passive"))
      (node (ref "R56") (pin "2") (pinfunction "2_2") (pintype "passive"))
      (node (ref "R57") (pin "2") (pinfunction "2_2") (pintype "passive"))
      (node (ref "R58") (pin "2") (pinfunction "2_2") (pintype "passive"))
      (node (ref "R6") (pin "2") (pinfunction "2_2") (pintype "passive"))
      (node (ref "X1") (pin "2") (pinfunction "GND_2") (pintype "power_in"))
      (node (ref "X3") (pin "2") (pinfunction "GND_2") (pintype "power_in"))
    )
    (net (code "6") (name "Net-(C1-Pad1)") (class "Default")
      (node (ref "C1") (pin "1") (pinfunction "1_1") (pintype "passive"))
      (node (ref "Q1") (pin "2") (pinfunction "2_2") (pintype "passive"))
      (node (ref "Q2") (pin "2") (pinfunction "2_2") (pintype "passive"))
      (node (ref "Q3") (pin "1") (pinfunction "1_1") (pintype "passive"))
    )
    (net (code "7") (name "Net-(C2-Pad1)") (class "Default")
      (node (ref "C2") (pin "1") (pinfunction "1_1") (pintype "passive"))
      (node (ref "Q3") (pin "2") (pinfunction "2_2") (pintype "passive"))
      (node (ref "Q4") (pin "1") (pinfunction "1_1") (pintype "passive"))
    )
    (net (code "8") (name "Net-(C3-Pad1)") (class "Default")
      (node (ref "C3") (pin "1") (pinfunction "1_1") (pintype "passive"))
      (node (ref "Q4") (pin "2") (pinfunction "2_2") (pintype "passive"))
      (node (ref "Q5") (pin "1") (pinfunction "1_1") (pintype "passive"))
    )
    (net (code "9") (name "Net-(C4-Pad1)") (class "Default")
      (node (ref "C4") (pin "1") (pinfunction "1_1") (pintype "passive"))
      (node (ref "Q5") (pin "2") (pinfunction "2_2") (pintype "passive"))
      (node (ref "Q6") (pin "1") (pinfunction "1_1") (pintype "passive"))
    )
    (net (code "10") (name "Net-(C5-Pad1)") (class "Default")
      (node (ref "C5") (pin "1") (pinfunction "1_1") (pintype "passive"))
      (node (ref "Q6") (pin "2") (pinfunction "2_2") (pintype "passive"))
      (node (ref "Q7") (pin "1") (pinfunction "1_1") (pintype "passive"))
      (node (ref "Q9") (pin "1") (pinfunction "1_1") (pintype "passive"))
    )
    (net (code "11") (name "Net-(C9-Pad2)") (class "Default")
      (node (ref "C9") (pin "2") (pinfunction "2_2") (pintype "passive"))
      (node (ref "R9") (pin "2") (pinfunction "2_2") (pintype "passive"))
    )
    (net (code "12") (name "Net-(C10-Pad2)") (class "Default")
      (node (ref "C10") (pin "2") (pinfunction "2_2") (pintype "passive"))
      (node (ref "R2") (pin "1") (pinfunction "1_1") (pintype "passive"))
    )
    (net (code "13") (name "Net-(C11-Pad1)") (class "Default")
      (node (ref "C11") (pin "1") (pinfunction "1_1") (pintype "passive"))
      (node (ref "C7") (pin "2") (pinfunction "2_2") (pintype "passive"))
      (node (ref "D1") (pin "C") (pinfunction "C_C") (pintype "passive"))
      (node (ref "D2") (pin "A") (pinfunction "A_A") (pintype "passive"))
      (node (ref "JP2") (pin "2") (pinfunction "2_2") (pintype "passive"))
    )
    (net (code "14") (name "Net-(C13-Pad2)") (class "Default")
      (node (ref "C13") (pin "2") (pinfunction "2_2") (pintype "passive"))
      (node (ref "R15") (pin "1") (pinfunction "1_1") (pintype "passive"))
      (node (ref "R16") (pin "2") (pinfunction "2_2") (pintype "passive"))
    )
    (net (code "15") (name "Net-(C15-Pad1)") (class "Default")
      (node (ref "C15") (pin "1") (pinfunction "1_1") (pintype "passive"))
      (node (ref "JP1") (pin "2") (pinfunction "2_2") (pintype "passive"))
    )
    (net (code "16") (name "Net-(C16-Pad1)") (class "Default")
      (node (ref "C16") (pin "1") (pinfunction "1_1") (pintype "passive"))
      (node (ref "R19") (pin "1") (pinfunction "1_1") (pintype "passive"))
    )
    (net (code "17") (name "Net-(C16-Pad2)") (class "Default")
      (node (ref "C16") (pin "2") (pinfunction "2_2") (pintype "passive"))
      (node (ref "C6") (pin "2") (pinfunction "2_2") (pintype "passive"))
      (node (ref "Q7") (pin "2") (pinfunction "2_2") (pintype "passive"))
      (node (ref "Q9") (pin "2") (pinfunction "2_2") (pintype "passive"))
    )
    (net (code "18") (name "Net-(C21-Pad+)") (class "Default")
      (node (ref "C21") (pin "+") (pinfunction "+_+") (pintype "passive"))
      (node (ref "R30") (pin "2") (pinfunction "2_2") (pintype "passive"))
      (node (ref "R31") (pin "1") (pinfunction "1_1") (pintype "passive"))
    )
    (net (code "19") (name "Net-(C22-Pad1)") (class "Default")
      (node (ref "C22") (pin "1") (pinfunction "1_1") (pintype "passive"))
      (node (ref "C35") (pin "-") (pinfunction "-_-") (pintype "passive"))
      (node (ref "C41") (pin "-") (pinfunction "-_-") (pintype "passive"))
      (node (ref "JP1") (pin "4") (pinfunction "4_4") (pintype "passive"))
      (node (ref "JP1") (pin "5") (pinfunction "5_5") (pintype "passive"))
      (node (ref "R60") (pin "2") (pinfunction "2_2") (pintype "passive"))
    )
    (net (code "20") (name "Net-(C24-Pad2)") (class "Default")
      (node (ref "C24") (pin "2") (pinfunction "2_2") (pintype "passive"))
      (node (ref "Q18") (pin "S") (pinfunction "S_S") (pintype "passive"))
      (node (ref "Q19") (pin "S") (pinfunction "S_S") (pintype "passive"))
      (node (ref "R25") (pin "2") (pinfunction "2_2") (pintype "passive"))
    )
    (net (code "21") (name "Net-(C25-Pad+)") (class "Default")
      (node (ref "C25") (pin "+") (pinfunction "+_+") (pintype "passive"))
      (node (ref "IC1") (pin "OUT") (pinfunction "OUT_OUT") (pintype "passive"))
      (node (ref "R26") (pin "A") (pinfunction "A_A") (pintype "passive"))
    )
    (net (code "22") (name "Net-(C26-E)") (class "Default")
      (node (ref "C26") (pin "1") (pinfunction "E_1") (pintype "passive"))
      (node (ref "K1") (pin "1") (pinfunction "O_1") (pintype "passive"))
    )
    (net (code "23") (name "Net-(C27-E)") (class "Default")
      (node (ref "C27") (pin "1") (pinfunction "E_1") (pintype "passive"))
      (node (ref "K1") (pin "10") (pinfunction "S_10") (pintype "passive"))
    )
    (net (code "24") (name "Net-(C28-Pad-)") (class "Default")
      (node (ref "C28") (pin "-") (pinfunction "-_-") (pintype "passive"))
      (node (ref "JP7") (pin "2") (pinfunction "2_2") (pintype "passive"))
    )
    (net (code "25") (name "Net-(C29-Pad+)") (class "Default")
      (node (ref "C29") (pin "+") (pinfunction "+_+") (pintype "passive"))
      (node (ref "JP5") (pin "2") (pinfunction "2_2") (pintype "passive"))
    )
    (net (code "26") (name "Net-(C29-Pad-)") (class "Default")
      (node (ref "C29") (pin "-") (pinfunction "-_-") (pintype "passive"))
      (node (ref "R27") (pin "2") (pinfunction "2_2") (pintype "passive"))
      (node (ref "R28") (pin "1") (pinfunction "1_1") (pintype "passive"))
    )
    (net (code "27") (name "Net-(C32-Pad+)") (class "Default")
      (node (ref "C32") (pin "+") (pinfunction "+_+") (pintype "passive"))
      (node (ref "R36") (pin "1") (pinfunction "1_1") (pintype "passive"))
      (node (ref "R37") (pin "2") (pinfunction "2_2") (pintype "passive"))
    )
    (net (code "28") (name "Net-(C37-Pad-)") (class "Default")
      (node (ref "C37") (pin "-") (pinfunction "-_-") (pintype "passive"))
      (node (ref "R44") (pin "1") (pinfunction "1_1") (pintype "passive"))
    )
    (net (code "29") (name "Net-(C38-Pad-)") (class "Default")
      (node (ref "C38") (pin "-") (pinfunction "-_-") (pintype "passive"))
      (node (ref "C39") (pin "2") (pinfunction "2_2") (pintype "passive"))
      (node (ref "JP6") (pin "1") (pinfunction "1_1") (pintype "passive"))
      (node (ref "R49") (pin "2") (pinfunction "2_2") (pintype "passive"))
    )
    (net (code "30") (name "Net-(C40-Pad+)") (class "Default")
      (node (ref "C40") (pin "+") (pinfunction "+_+") (pintype "passive"))
      (node (ref "R46") (pin "1") (pinfunction "1_1") (pintype "passive"))
      (node (ref "R47") (pin "1") (pinfunction "1_1") (pintype "passive"))
      (node (ref "R48") (pin "1") (pinfunction "1_1") (pintype "passive"))
      (node (ref "R49") (pin "1") (pinfunction "1_1") (pintype "passive"))
    )
    (net (code "31") (name "Net-(C43-Pad+)") (class "Default")
      (node (ref "C43") (pin "+") (pinfunction "+_+") (pintype "passive"))
      (node (ref "R51") (pin "2") (pinfunction "2_2") (pintype "passive"))
      (node (ref "R53") (pin "1") (pinfunction "1_1") (pintype "passive"))
    )
    (net (code "32") (name "Net-(C46-Pad+)") (class "Default")
      (node (ref "C46") (pin "+") (pinfunction "+_+") (pintype "passive"))
      (node (ref "R54") (pin "1") (pinfunction "1_1") (pintype "passive"))
      (node (ref "R55") (pin "1") (pinfunction "1_1") (pintype "passive"))
    )
    (net (code "33") (name "Net-(C47-Pad1)") (class "Default")
      (node (ref "C47") (pin "1") (pinfunction "1_1") (pintype "passive"))
      (node (ref "C48") (pin "2") (pinfunction "2_2") (pintype "passive"))
      (node (ref "R57") (pin "1") (pinfunction "1_1") (pintype "passive"))
    )
    (net (code "34") (name "Net-(C48-Pad1)") (class "Default")
      (node (ref "C48") (pin "1") (pinfunction "1_1") (pintype "passive"))
      (node (ref "C49") (pin "2") (pinfunction "2_2") (pintype "passive"))
      (node (ref "R58") (pin "1") (pinfunction "1_1") (pintype "passive"))
    )
    (net (code "35") (name "Net-(C57-E)") (class "Default")
      (node (ref "C57") (pin "1") (pinfunction "E_1") (pintype "passive"))
      (node (ref "LP10") (pin "1") (pinfunction "1_1") (pintype "passive"))
    )
    (net (code "36") (name "Net-(C58-Pad1)") (class "Default")
      (node (ref "C58") (pin "1") (pinfunction "1_1") (pintype "passive"))
      (node (ref "LP10") (pin "2") (pinfunction "2_2") (pintype "passive"))
      (node (ref "LP6") (pin "2") (pinfunction "2_2") (pintype "passive"))
      (node (ref "LP7") (pin "1") (pinfunction "1_1") (pintype "passive"))
    )
    (net (code "37") (name "Net-(C59-Pad1)") (class "Default")
      (node (ref "C59") (pin "1") (pinfunction "1_1") (pintype "passive"))
      (node (ref "LP11") (pin "2") (pinfunction "2_2") (pintype "passive"))
      (node (ref "LP7") (pin "2") (pinfunction "2_2") (pintype "passive"))
      (node (ref "LP8") (pin "1") (pinfunction "1_1") (pintype "passive"))
    )
    (net (code "38") (name "Net-(C60-Pad1)") (class "Default")
      (node (ref "C60") (pin "1") (pinfunction "1_1") (pintype "passive"))
      (node (ref "LP12") (pin "2") (pinfunction "2_2") (pintype "passive"))
      (node (ref "LP8") (pin "2") (pinfunction "2_2") (pintype "passive"))
      (node (ref "LP9") (pin "1") (pinfunction "1_1") (pintype "passive"))
    )
    (net (code "39") (name "Net-(C63-Pad1)") (class "Default")
      (node (ref "C63") (pin "1") (pinfunction "1_1") (pintype "passive"))
      (node (ref "LP1") (pin "2") (pinfunction "2_2") (pintype "passive"))
      (node (ref "LP2") (pin "1") (pinfunction "1_1") (pintype "passive"))
    )
    (net (code "40") (name "Net-(C64-Pad1)") (class "Default")
      (node (ref "C64") (pin "1") (pinfunction "1_1") (pintype "passive"))
      (node (ref "LP2") (pin "2") (pinfunction "2_2") (pintype "passive"))
      (node (ref "LP3") (pin "1") (pinfunction "1_1") (pintype "passive"))
    )
    (net (code "41") (name "Net-(C65-Pad1)") (class "Default")
      (node (ref "C65") (pin "1") (pinfunction "1_1") (pintype "passive"))
      (node (ref "LP3") (pin "2") (pinfunction "2_2") (pintype "passive"))
      (node (ref "LP4") (pin "1") (pinfunction "1_1") (pintype "passive"))
    )
    (net (code "42") (name "Net-(C66-Pad1)") (class "Default")
      (node (ref "C66") (pin "1") (pinfunction "1_1") (pintype "passive"))
      (node (ref "LP4") (pin "2") (pinfunction "2_2") (pintype "passive"))
      (node (ref "LP5") (pin "1") (pinfunction "1_1") (pintype "passive"))
    )
    (net (code "43") (name "Net-(C68-E)") (class "Default")
      (node (ref "C68") (pin "1") (pinfunction "E_1") (pintype "passive"))
      (node (ref "LP11") (pin "1") (pinfunction "1_1") (pintype "passive"))
    )
    (net (code "44") (name "Net-(C69-E)") (class "Default")
      (node (ref "C69") (pin "1") (pinfunction "E_1") (pintype "passive"))
      (node (ref "LP12") (pin "1") (pinfunction "1_1") (pintype "passive"))
    )
    (net (code "45") (name "Net-(D1-PadA)") (class "Default")
      (node (ref "D1") (pin "A") (pinfunction "A_A") (pintype "passive"))
      (node (ref "JP1") (pin "6") (pinfunction "6_6") (pintype "passive"))
    )
    (net (code "46") (name "Net-(D2-PadC)") (class "Default")
      (node (ref "D2") (pin "C") (pinfunction "C_C") (pintype "passive"))
      (node (ref "JP1") (pin "3") (pinfunction "3_3") (pintype "passive"))
    )
    (net (code "47") (name "Net-(D3-PadC)") (class "Default")
      (node (ref "D3") (pin "C") (pinfunction "C_C") (pintype "passive"))
      (node (ref "D4") (pin "A") (pinfunction "A_A") (pintype "passive"))
    )
    (net (code "48") (name "Net-(JP3-Pad3)") (class "Default")
      (node (ref "JP3") (pin "3") (pinfunction "3_3") (pintype "passive"))
      (node (ref "Q18") (pin "D") (pinfunction "D_D") (pintype "passive"))
    )
    (net (code "49") (name "Net-(JP3-Pad4)") (class "Default")
      (node (ref "JP3") (pin "4") (pinfunction "4_4") (pintype "passive"))
      (node (ref "JP3") (pin "5") (pinfunction "5_5") (pintype "passive"))
      (node (ref "Q1") (pin "1") (pinfunction "1_1") (pintype "passive"))
      (node (ref "Q2") (pin "1") (pinfunction "1_1") (pintype "passive"))
    )
    (net (code "50") (name "Net-(JP3-Pad6)") (class "Default")
      (node (ref "JP3") (pin "6") (pinfunction "6_6") (pintype "passive"))
      (node (ref "Q19") (pin "D") (pinfunction "D_D") (pintype "passive"))
    )
    (net (code "51") (name "Net-(JP4-Pad2)") (class "Default")
      (node (ref "JP4") (pin "2") (pinfunction "2_2") (pintype "passive"))
      (node (ref "X1") (pin "1") (pinfunction "1_1") (pintype "passive"))
    )
    (net (code "52") (name "Net-(JP4-Pad4)") (class "Default")
      (node (ref "JP4") (pin "4") (pinfunction "4_4") (pintype "passive"))
      (node (ref "Q18") (pin "G") (pinfunction "G_G") (pintype "passive"))
    )
    (net (code "53") (name "Net-(JP4-Pad5)") (class "Default")
      (node (ref "JP4") (pin "5") (pinfunction "5_5") (pintype "passive"))
      (node (ref "Q19") (pin "G") (pinfunction "G_G") (pintype "passive"))
    )
    (net (code "54") (name "Net-(JP9-Pad1)") (class "Default")
      (node (ref "JP9") (pin "1") (pinfunction "1_1") (pintype "passive"))
      (node (ref "R52") (pin "1") (pinfunction "1_1") (pintype "passive"))
    )
    (net (code "55") (name "Net-(JP10-Pad1)") (class "Default")
      (node (ref "JP10") (pin "1") (pinfunction "1_1") (pintype "passive"))
      (node (ref "R59") (pin "2") (pinfunction "2_2") (pintype "passive"))
    )
    (net (code "56") (name "Net-(JP27-Pad1)") (class "Default")
      (node (ref "JP27") (pin "1") (pinfunction "1_1") (pintype "passive"))
      (node (ref "R64") (pin "1") (pinfunction "1_1") (pintype "passive"))
    )
    (net (code "57") (name "Net-(K1A-2)") (class "Default")
      (node (ref "C44") (pin "1") (pinfunction "1_1") (pintype "passive"))
      (node (ref "D5") (pin "A") (pinfunction "A_A") (pintype "passive"))
      (node (ref "K1") (pin "9") (pinfunction "2_9") (pintype "passive"))
      (node (ref "Q27") (pin "1") (pinfunction "C_1") (pintype "passive"))
    )
    (net (code "58") (name "Net-(K1B-P-Pad5)") (class "Default")
      (node (ref "K1") (pin "5") (pinfunction "P_5") (pintype "passive"))
      (node (ref "L1") (pin "2") (pinfunction "2_2") (pintype "passive"))
    )
    (net (code "59") (name "Net-(K2A-O)") (class "Default")
      (node (ref "C50") (pin "-") (pinfunction "-_-") (pintype "passive"))
      (node (ref "K2") (pin "6") (pinfunction "O_6") (pintype "passive"))
    )
    (net (code "60") (name "Net-(K2A-P)") (class "Default")
      (node (ref "JP7") (pin "3") (pinfunction "3_3") (pintype "passive"))
      (node (ref "K2") (pin "4") (pinfunction "P_4") (pintype "passive"))
    )
    (net (code "61") (name "Net-(K2A-S)") (class "Default")
      (node (ref "K2") (pin "8") (pinfunction "S_8") (pintype "passive"))
      (node (ref "R61") (pin "2") (pinfunction "2_2") (pintype "passive"))
    )
    (net (code "62") (name "Net-(K3A-2)") (class "Default")
      (node (ref "C70") (pin "1") (pinfunction "1_1") (pintype "passive"))
      (node (ref "C71") (pin "1") (pinfunction "1_1") (pintype "passive"))
      (node (ref "D7") (pin "A") (pinfunction "A_A") (pintype "passive"))
      (node (ref "K3") (pin "9") (pinfunction "2_9") (pintype "passive"))
      (node (ref "K4") (pin "9") (pinfunction "2_9") (pintype "passive"))
      (node (ref "Q39") (pin "1") (pinfunction "C_1") (pintype "passive"))
    )
    (net (code "63") (name "Net-(K3B-O)") (class "Default")
      (node (ref "C62") (pin "1") (pinfunction "1_1") (pintype "passive"))
      (node (ref "K3") (pin "1") (pinfunction "O_1") (pintype "passive"))
      (node (ref "LP1") (pin "1") (pinfunction "1_1") (pintype "passive"))
    )
    (net (code "64") (name "Net-(K3B-S)") (class "Default")
      (node (ref "C56") (pin "1") (pinfunction "1_1") (pintype "passive"))
      (node (ref "K3") (pin "10") (pinfunction "S_10") (pintype "passive"))
      (node (ref "LP6") (pin "1") (pinfunction "1_1") (pintype "passive"))
    )
    (net (code "65") (name "Net-(K4B-O)") (class "Default")
      (node (ref "C67") (pin "1") (pinfunction "1_1") (pintype "passive"))
      (node (ref "K4") (pin "1") (pinfunction "O_1") (pintype "passive"))
      (node (ref "LP5") (pin "2") (pinfunction "2_2") (pintype "passive"))
    )
    (net (code "66") (name "Net-(K4B-P-Pad6)") (class "Default")
      (node (ref "K4") (pin "6") (pinfunction "P_6") (pintype "passive"))
      (node (ref "X3") (pin "1") (pinfunction "1_1") (pintype "passive"))
    )
    (net (code "67") (name "Net-(K4B-S)") (class "Default")
      (node (ref "C61") (pin "1") (pinfunction "1_1") (pintype "passive"))
      (node (ref "K4") (pin "10") (pinfunction "S_10") (pintype "passive"))
      (node (ref "LP9") (pin "2") (pinfunction "2_2") (pintype "passive"))
    )
    (net (code "68") (name "Net-(L1-Pad1)") (class "Default")
      (node (ref "L1") (pin "1") (pinfunction "1_1") (pintype "passive"))
      (node (ref "Q17") (pin "1") (pinfunction "1_1") (pintype "passive"))
    )
    (net (code "69") (name "Net-(Q8-B)") (class "Default")
      (node (ref "C7") (pin "1") (pinfunction "1_1") (pintype "passive"))
      (node (ref "C9") (pin "1") (pinfunction "1_1") (pintype "passive"))
      (node (ref "Q8") (pin "2") (pinfunction "B_2") (pintype "passive"))
      (node (ref "R6") (pin "1") (pinfunction "1_1") (pintype "passive"))
      (node (ref "R8") (pin "1") (pinfunction "1_1") (pintype "passive"))
    )
    (net (code "70") (name "Net-(Q8-E)") (class "Default")
      (node (ref "C10") (pin "1") (pinfunction "1_1") (pintype "passive"))
      (node (ref "Q8") (pin "3") (pinfunction "E_3") (pintype "passive"))
      (node (ref "R4") (pin "1") (pinfunction "1_1") (pintype "passive"))
    )
    (net (code "71") (name "Net-(Q10-B)") (class "Default")
      (node (ref "Q10") (pin "2") (pinfunction "B_2") (pintype "passive"))
      (node (ref "Q8") (pin "1") (pinfunction "C_1") (pintype "passive"))
      (node (ref "R5") (pin "1") (pinfunction "1_1") (pintype "passive"))
      (node (ref "R9") (pin "1") (pinfunction "1_1") (pintype "passive"))
    )
    (net (code "72") (name "Net-(Q10-C)") (class "Default")
      (node (ref "C8") (pin "1") (pinfunction "1_1") (pintype "passive"))
      (node (ref "Q10") (pin "1") (pinfunction "C_1") (pintype "passive"))
      (node (ref "Q11") (pin "1") (pinfunction "C_1") (pintype "passive"))
      (node (ref "R5") (pin "2") (pinfunction "2_2") (pintype "passive"))
      (node (ref "R7") (pin "2") (pinfunction "2_2") (pintype "passive"))
      (node (ref "R8") (pin "2") (pinfunction "2_2") (pintype "passive"))
    )
    (net (code "73") (name "Net-(Q10-E)") (class "Default")
      (node (ref "Q10") (pin "3") (pinfunction "E_3") (pintype "passive"))
      (node (ref "Q11") (pin "2") (pinfunction "B_2") (pintype "passive"))
      (node (ref "R3") (pin "1") (pinfunction "1_1") (pintype "passive"))
    )
    (net (code "74") (name "Net-(Q11-E)") (class "Default")
      (node (ref "Q11") (pin "3") (pinfunction "E_3") (pintype "passive"))
      (node (ref "R1") (pin "1") (pinfunction "1_1") (pintype "passive"))
      (node (ref "R19") (pin "2") (pinfunction "2_2") (pintype "passive"))
    )
    (net (code "75") (name "Net-(Q12-B)") (class "Default")
      (node (ref "Q12") (pin "2") (pinfunction "B_2") (pintype "passive"))
      (node (ref "Q13") (pin "3") (pinfunction "E_3") (pintype "passive"))
      (node (ref "R11") (pin "1") (pinfunction "1_1") (pintype "passive"))
    )
    (net (code "76") (name "Net-(Q12-C)") (class "Default")
      (node (ref "C14") (pin "2") (pinfunction "2_2") (pintype "passive"))
      (node (ref "Q12") (pin "1") (pinfunction "C_1") (pintype "passive"))
      (node (ref "Q13") (pin "1") (pinfunction "C_1") (pintype "passive"))
      (node (ref "R14") (pin "1") (pinfunction "1_1") (pintype "passive"))
      (node (ref "R16") (pin "1") (pinfunction "1_1") (pintype "passive"))
      (node (ref "R17") (pin "1") (pinfunction "1_1") (pintype "passive"))
    )
    (net (code "77") (name "Net-(Q12-E)") (class "Default")
      (node (ref "C11") (pin "2") (pinfunction "2_2") (pintype "passive"))
      (node (ref "Q12") (pin "3") (pinfunction "E_3") (pintype "passive"))
      (node (ref "R12") (pin "1") (pinfunction "1_1") (pintype "passive"))
    )
    (net (code "78") (name "Net-(Q13-B)") (class "Default")
      (node (ref "Q13") (pin "2") (pinfunction "B_2") (pintype "passive"))
      (node (ref "Q14") (pin "1") (pinfunction "C_1") (pintype "passive"))
      (node (ref "R15") (pin "2") (pinfunction "2_2") (pintype "passive"))
    )
    (net (code "79") (name "Net-(Q14-B)") (class "Default")
      (node (ref "C12") (pin "2") (pinfunction "2_2") (pintype "passive"))
      (node (ref "Q14") (pin "2") (pinfunction "B_2") (pintype "passive"))
      (node (ref "R13") (pin "1") (pinfunction "1_1") (pintype "passive"))
      (node (ref "R14") (pin "2") (pinfunction "2_2") (pintype "passive"))
    )
    (net (code "80") (name "Net-(Q14-E)") (class "Default")
      (node (ref "C6") (pin "1") (pinfunction "1_1") (pintype "passive"))
      (node (ref "Q14") (pin "3") (pinfunction "E_3") (pintype "passive"))
      (node (ref "R10") (pin "1") (pinfunction "1_1") (pintype "passive"))
    )
    (net (code "81") (name "Net-(Q15-B)") (class "Default")
      (node (ref "Q15") (pin "2") (pinfunction "B_2") (pintype "passive"))
      (node (ref "R20") (pin "2") (pinfunction "2_2") (pintype "passive"))
    )
    (net (code "82") (name "Net-(Q15-C)") (class "Default")
      (node (ref "C19") (pin "1") (pinfunction "1_1") (pintype "passive"))
      (node (ref "Q15") (pin "1") (pinfunction "C_1") (pintype "passive"))
      (node (ref "Q16") (pin "1") (pinfunction "C_1") (pintype "passive"))
      (node (ref "R23") (pin "1") (pinfunction "1_1") (pintype "passive"))
      (node (ref "R24") (pin "1") (pinfunction "1_1") (pintype "passive"))
    )
    (net (code "83") (name "Net-(Q15-E)") (class "Default")
      (node (ref "C15") (pin "2") (pinfunction "2_2") (pintype "passive"))
      (node (ref "Q15") (pin "3") (pinfunction "E_3") (pintype "passive"))
      (node (ref "R18") (pin "1") (pinfunction "1_1") (pintype "passive"))
    )
    (net (code "84") (name "Net-(Q16-B)") (class "Default")
      (node (ref "C18") (pin "1") (pinfunction "1_1") (pintype "passive"))
      (node (ref "Q16") (pin "2") (pinfunction "B_2") (pintype "passive"))
      (node (ref "Q17") (pin "2") (pinfunction "2_2") (pintype "passive"))
      (node (ref "R22") (pin "1") (pinfunction "1_1") (pintype "passive"))
      (node (ref "R23") (pin "2") (pinfunction "2_2") (pintype "passive"))
    )
    (net (code "85") (name "Net-(Q16-E)") (class "Default")
      (node (ref "C17") (pin "1") (pinfunction "1_1") (pintype "passive"))
      (node (ref "C18") (pin "2") (pinfunction "2_2") (pintype "passive"))
      (node (ref "Q16") (pin "3") (pinfunction "E_3") (pintype "passive"))
      (node (ref "R20") (pin "1") (pinfunction "1_1") (pintype "passive"))
      (node (ref "R21") (pin "1") (pinfunction "1_1") (pintype "passive"))
    )
    (net (code "86") (name "Net-(Q20-B)") (class "Default")
      (node (ref "C20") (pin "+") (pinfunction "+_+") (pintype "passive"))
      (node (ref "D3") (pin "A") (pinfunction "A_A") (pintype "passive"))
      (node (ref "Q20") (pin "2") (pinfunction "B_2") (pintype "passive"))
      (node (ref "R29") (pin "2") (pinfunction "2_2") (pintype "passive"))
    )
    (net (code "87") (name "Net-(Q20-C)") (class "Default")
      (node (ref "C30") (pin "+") (pinfunction "+_+") (pintype "passive"))
      (node (ref "Q20") (pin "1") (pinfunction "C_1") (pintype "passive"))
      (node (ref "R29") (pin "1") (pinfunction "1_1") (pintype "passive"))
      (node (ref "R32") (pin "1") (pinfunction "1_1") (pintype "passive"))
      (node (ref "R34") (pin "2") (pinfunction "2_2") (pintype "passive"))
    )
    (net (code "88") (name "Net-(Q20-E)") (class "Default")
      (node (ref "Q20") (pin "3") (pinfunction "E_3") (pintype "passive"))
      (node (ref "R27") (pin "1") (pinfunction "1_1") (pintype "passive"))
    )
    (net (code "89") (name "Net-(Q21-B)") (class "Default")
      (node (ref "C20") (pin "-") (pinfunction "-_-") (pintype "passive"))
      (node (ref "D4") (pin "C") (pinfunction "C_C") (pintype "passive"))
      (node (ref "Q21") (pin "2") (pinfunction "B_2") (pintype "passive"))
      (node (ref "Q22") (pin "1") (pinfunction "C_1") (pintype "passive"))
    )
    (net (code "90") (name "Net-(Q21-E)") (class "Default")
      (node (ref "Q21") (pin "3") (pinfunction "E_3") (pintype "passive"))
      (node (ref "R28") (pin "2") (pinfunction "2_2") (pintype "passive"))
    )
    (net (code "91") (name "Net-(Q22-B)") (class "Default")
      (node (ref "C28") (pin "+") (pinfunction "+_+") (pintype "passive"))
      (node (ref "Q22") (pin "2") (pinfunction "B_2") (pintype "passive"))
      (node (ref "R32") (pin "2") (pinfunction "2_2") (pintype "passive"))
      (node (ref "R33") (pin "1") (pinfunction "1_1") (pintype "passive"))
    )
    (net (code "92") (name "Net-(Q22-E)") (class "Default")
      (node (ref "Q22") (pin "3") (pinfunction "E_3") (pintype "passive"))
      (node (ref "R30") (pin "1") (pinfunction "1_1") (pintype "passive"))
    )
    (net (code "93") (name "Net-(Q23-B)") (class "Default")
      (node (ref "C31") (pin "+") (pinfunction "+_+") (pintype "passive"))
      (node (ref "Q23") (pin "2") (pinfunction "B_2") (pintype "passive"))
      (node (ref "R35") (pin "1") (pinfunction "1_1") (pintype "passive"))
    )
    (net (code "94") (name "Net-(Q23-E)") (class "Default")
      (node (ref "Q23") (pin "3") (pinfunction "E_3") (pintype "passive"))
      (node (ref "R36") (pin "2") (pinfunction "2_2") (pintype "passive"))
      (node (ref "R39") (pin "2") (pinfunction "2_2") (pintype "passive"))
      (node (ref "R41") (pin "2") (pinfunction "2_2") (pintype "passive"))
    )
    (net (code "95") (name "Net-(Q24-B)") (class "Default")
      (node (ref "Q24") (pin "2") (pinfunction "B_2") (pintype "passive"))
      (node (ref "Q25") (pin "1") (pinfunction "C_1") (pintype "passive"))
      (node (ref "R39") (pin "1") (pinfunction "1_1") (pintype "passive"))
    )
    (net (code "96") (name "Net-(Q24-C)") (class "Default")
      (node (ref "C50") (pin "+") (pinfunction "+_+") (pintype "passive"))
      (node (ref "Q24") (pin "1") (pinfunction "C_1") (pintype "passive"))
      (node (ref "R37") (pin "1") (pinfunction "1_1") (pintype "passive"))
    )
    (net (code "97") (name "Net-(Q24-E)") (class "Default")
      (node (ref "C33") (pin "+") (pinfunction "+_+") (pintype "passive"))
      (node (ref "Q24") (pin "3") (pinfunction "E_3") (pintype "passive"))
      (node (ref "R38") (pin "2") (pinfunction "2_2") (pintype "passive"))
    )
    (net (code "98") (name "Net-(Q25-B)") (class "Default")
      (node (ref "C36") (pin "+") (pinfunction "+_+") (pintype "passive"))
      (node (ref "Q25") (pin "2") (pinfunction "B_2") (pintype "passive"))
      (node (ref "R41") (pin "1") (pinfunction "1_1") (pintype "passive"))
      (node (ref "R42") (pin "1") (pinfunction "1_1") (pintype "passive"))
    )
    (net (code "99") (name "Net-(Q25-E)") (class "Default")
      (node (ref "C35") (pin "+") (pinfunction "+_+") (pintype "passive"))
      (node (ref "Q25") (pin "3") (pinfunction "E_3") (pintype "passive"))
      (node (ref "R40") (pin "2") (pinfunction "2_2") (pintype "passive"))
    )
    (net (code "100") (name "Net-(Q26-B)") (class "Default")
      (node (ref "C38") (pin "+") (pinfunction "+_+") (pintype "passive"))
      (node (ref "Q26") (pin "2") (pinfunction "B_2") (pintype "passive"))
      (node (ref "R45") (pin "1") (pinfunction "1_1") (pintype "passive"))
      (node (ref "R46") (pin "2") (pinfunction "2_2") (pintype "passive"))
    )
    (net (code "101") (name "Net-(Q26-C)") (class "Default")
      (node (ref "C41") (pin "+") (pinfunction "+_+") (pintype "passive"))
      (node (ref "Q26") (pin "1") (pinfunction "C_1") (pintype "passive"))
      (node (ref "R47") (pin "2") (pinfunction "2_2") (pintype "passive"))
    )
    (net (code "102") (name "Net-(Q26-E)") (class "Default")
      (node (ref "C37") (pin "+") (pinfunction "+_+") (pintype "passive"))
      (node (ref "Q26") (pin "3") (pinfunction "E_3") (pintype "passive"))
      (node (ref "R43") (pin "1") (pinfunction "1_1") (pintype "passive"))
    )
    (net (code "103") (name "Net-(Q27-B)") (class "Default")
      (node (ref "Q27") (pin "2") (pinfunction "B_2") (pintype "passive"))
      (node (ref "R52") (pin "2") (pinfunction "2_2") (pintype "passive"))
    )
    (net (code "104") (name "Net-(Q28-B)") (class "Default")
      (node (ref "JP8") (pin "1") (pinfunction "1_1") (pintype "passive"))
      (node (ref "Q28") (pin "2") (pinfunction "B_2") (pintype "passive"))
    )
    (net (code "105") (name "Net-(Q28-C)") (class "Default")
      (node (ref "Q28") (pin "1") (pinfunction "C_1") (pintype "passive"))
      (node (ref "Q29") (pin "2") (pinfunction "B_2") (pintype "passive"))
      (node (ref "R50") (pin "2") (pinfunction "2_2") (pintype "passive"))
    )
    (net (code "106") (name "Net-(Q29-C)") (class "Default")
      (node (ref "C23") (pin "1") (pinfunction "1_1") (pintype "passive"))
      (node (ref "D6") (pin "A") (pinfunction "A_A") (pintype "passive"))
      (node (ref "K2") (pin "1") (pinfunction "1_1") (pintype "passive"))
      (node (ref "Q29") (pin "1") (pinfunction "C_1") (pintype "passive"))
    )
    (net (code "107") (name "Net-(Q30-B)") (class "Default")
      (node (ref "C47") (pin "2") (pinfunction "2_2") (pintype "passive"))
      (node (ref "Q30") (pin "2") (pinfunction "B_2") (pintype "passive"))
      (node (ref "R56") (pin "1") (pinfunction "1_1") (pintype "passive"))
      (node (ref "R59") (pin "1") (pinfunction "1_1") (pintype "passive"))
    )
    (net (code "108") (name "Net-(Q30-C)") (class "Default")
      (node (ref "C49") (pin "1") (pinfunction "1_1") (pintype "passive"))
      (node (ref "Q30") (pin "1") (pinfunction "C_1") (pintype "passive"))
      (node (ref "R54") (pin "2") (pinfunction "2_2") (pintype "passive"))
    )
    (net (code "109") (name "Net-(Q30-E)") (class "Default")
      (node (ref "Q30") (pin "3") (pinfunction "E_3") (pintype "passive"))
      (node (ref "R51") (pin "1") (pinfunction "1_1") (pintype "passive"))
      (node (ref "R60") (pin "1") (pinfunction "1_1") (pintype "passive"))
      (node (ref "R61") (pin "1") (pinfunction "1_1") (pintype "passive"))
    )
    (net (code "110") (name "Net-(Q39-B)") (class "Default")
      (node (ref "Q39") (pin "2") (pinfunction "B_2") (pintype "passive"))
      (node (ref "R64") (pin "2") (pinfunction "2_2") (pintype "passive"))
    )
    (net (code "111") (name "Net-(R25-Pad1)") (class "Default")
      (node (ref "R25") (pin "1") (pinfunction "1_1") (pintype "passive"))
      (node (ref "R26") (pin "S") (pinfunction "S_S") (pintype "passive"))
    )
    (net (code "112") (name "unconnected-(H1-MOUNT-PadB3,0)") (class "Default")
      (node (ref "H1") (pin "B3,0") (pinfunction "MOUNT_B3,0") (pintype "passive"))
    )
    (net (code "113") (name "unconnected-(H2-MOUNT-PadB3,0)") (class "Default")
      (node (ref "H2") (pin "B3,0") (pinfunction "MOUNT_B3,0") (pintype "passive"))
    )
    (net (code "114") (name "unconnected-(H3-MOUNT-PadB3,0)") (class "Default")
      (node (ref "H3") (pin "B3,0") (pinfunction "MOUNT_B3,0") (pintype "passive"))
    )
    (net (code "115") (name "unconnected-(H4-MOUNT-PadB3,0)") (class "Default")
      (node (ref "H4") (pin "B3,0") (pinfunction "MOUNT_B3,0") (pintype "passive"))
    )
    (net (code "116") (name "unconnected-(K1B-P-Pad6)") (class "Default")
      (node (ref "K1") (pin "6") (pinfunction "P_6") (pintype "passive"))
    )
    (net (code "117") (name "unconnected-(K3B-P-Pad6)") (class "Default")
      (node (ref "K3") (pin "6") (pinfunction "P_6") (pintype "passive"))
    )
    (net (code "118") (name "unconnected-(K4B-P-Pad5)") (class "Default")
      (node (ref "K4") (pin "5") (pinfunction "P_5") (pintype "passive"))
    )
  )
)
